# Digital__IO.net
KiCad netlist of a schematic drawn in Altium Designer
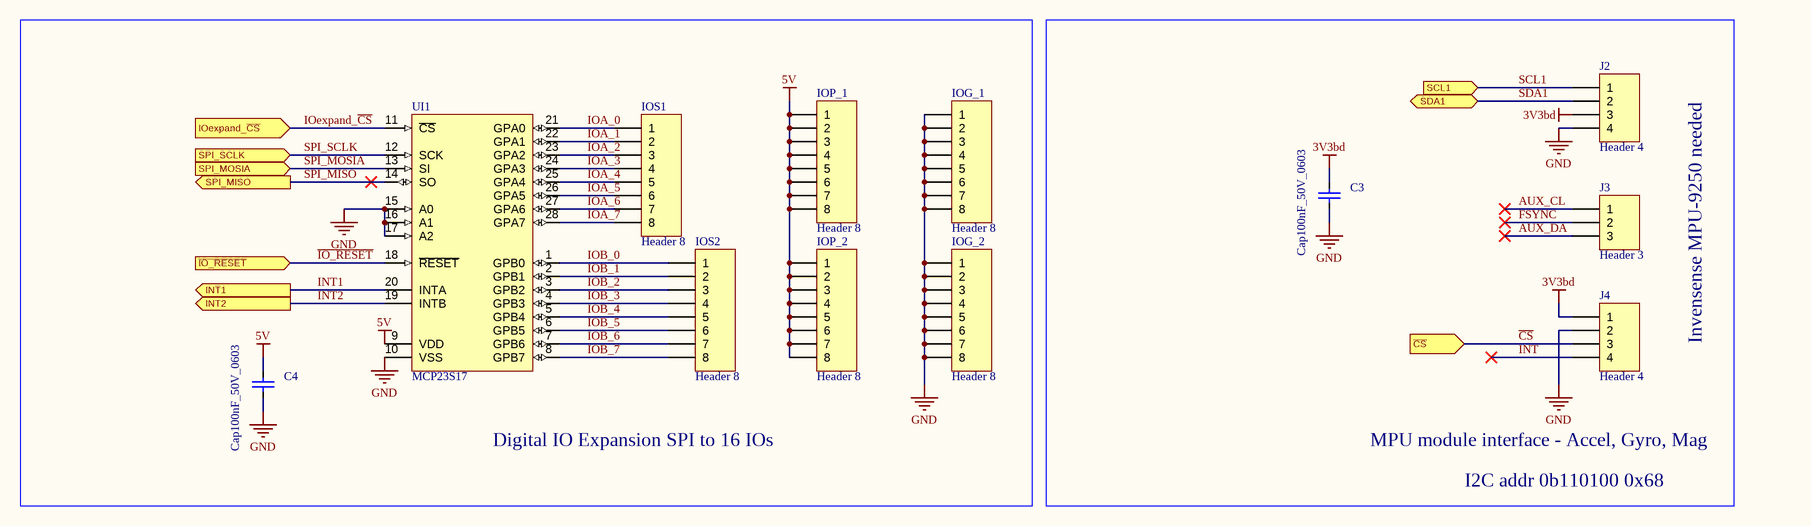
[diagram p0: Digital_ IO.SchDoc]

(export (version "E")
  (design (tool "Eeschema 10.0.6"))
  (components
    (comp (ref "C3")
      (value "Cap100nF_50V_0603")
      (footprint "0603C_L")
      (libsource (lib " Advanced] Training Course - A365") (part "CAP General"))
    )
    (comp (ref "C4")
      (value "Cap100nF_50V_0603")
      (footprint "0603C_L")
      (libsource (lib " Advanced] Training Course - A365") (part "CAP General"))
    )
    (comp (ref "IOG_1")
      (value "Header 8")
      (footprint "HDR1X8")
      (description "Header, 8-Pin")
      (fields (field (name "PUBLISHER") "Altium Limited") (field (name "SOURCE") "WCT.SchLib"))
      (libsource (lib " Advanced] Training Course - A365") (part "Header 8"))
    )
    (comp (ref "IOG_2")
      (value "Header 8")
      (footprint "HDR1X8")
      (description "Header, 8-Pin")
      (fields (field (name "PUBLISHER") "Altium Limited") (field (name "SOURCE") "WCT.SchLib"))
      (libsource (lib " Advanced] Training Course - A365") (part "Header 8"))
    )
    (comp (ref "IOP_1")
      (value "Header 8")
      (footprint "HDR1X8")
      (description "Header, 8-Pin")
      (fields (field (name "PUBLISHER") "Altium Limited") (field (name "SOURCE") "WCT.SchLib"))
      (libsource (lib " Advanced] Training Course - A365") (part "Header 8"))
    )
    (comp (ref "IOP_2")
      (value "Header 8")
      (footprint "HDR1X8")
      (description "Header, 8-Pin")
      (fields (field (name "PUBLISHER") "Altium Limited") (field (name "SOURCE") "WCT.SchLib"))
      (libsource (lib " Advanced] Training Course - A365") (part "Header 8"))
    )
    (comp (ref "IOS1")
      (value "Header 8")
      (footprint "HDR1X8")
      (description "Header, 8-Pin")
      (fields (field (name "PUBLISHER") "Altium Limited") (field (name "SOURCE") "WCT.SchLib"))
      (libsource (lib " Advanced] Training Course - A365") (part "Header 8"))
    )
    (comp (ref "IOS2")
      (value "Header 8")
      (footprint "HDR1X8")
      (description "Header, 8-Pin")
      (fields (field (name "PUBLISHER") "Altium Limited") (field (name "SOURCE") "WCT.SchLib"))
      (libsource (lib " Advanced] Training Course - A365") (part "Header 8"))
    )
    (comp (ref "J2")
      (value "Header 4")
      (footprint "HDR1X4")
      (description "Header, 4-Pin")
      (fields (field (name "PUBLISHER") "Altium Limited") (field (name "SOURCE") "WCT.SchLib"))
      (libsource (lib " Advanced] Training Course - A365") (part "Header 4"))
    )
    (comp (ref "J3")
      (value "Header 3")
      (footprint "HDR1X3")
      (description "Header, 3-Pin")
      (fields (field (name "PUBLISHER") "Altium Limited") (field (name "SOURCE") "WCT.SchLib"))
      (libsource (lib " Advanced] Training Course - A365") (part "Header 3"))
    )
    (comp (ref "J4")
      (value "Header 4")
      (footprint "HDR1X4")
      (description "Header, 4-Pin")
      (fields (field (name "PUBLISHER") "Altium Limited") (field (name "SOURCE") "WCT.SchLib"))
      (libsource (lib " Advanced] Training Course - A365") (part "Header 4"))
    )
    (comp (ref "UI1")
      (value "MCP23S17")
      (footprint "SOIC-SO28_L")
      (description "16-Bit I/O Expander with Serial Interface, 28-Pin SOIC, Extended Temperature, Tape and Reel")
      (fields
        (field (name "MANUFACTURER") "Microchip")
        (field (name "MANUFACTURER PART NUMBER") "MCP23S17T-E/SO")
        (field (name "AVAILABLE PREVIEW IMAGES") "2D")
        (field (name "SOURCE") "WCT.SchLib")
      )
      (libsource (lib " Advanced] Training Course - A365") (part "MCP23S17"))
    )
  )
  (nets
    (net (code "1") (name "/AUX_CL") (class "Default")
      (node (ref "J3") (pin "1") (pinfunction "1_1") (pintype "passive+no_connect"))
    )
    (net (code "2") (name "/AUX_DA") (class "Default")
      (node (ref "J3") (pin "3") (pinfunction "3_3") (pintype "passive+no_connect"))
    )
    (net (code "3") (name "/FSYNC") (class "Default")
      (node (ref "J3") (pin "2") (pinfunction "2_2") (pintype "passive+no_connect"))
    )
    (net (code "4") (name "/INT") (class "Default")
      (node (ref "J4") (pin "4") (pinfunction "4_4") (pintype "passive+no_connect"))
    )
    (net (code "5") (name "/INT1") (class "Default")
      (node (ref "UI1") (pin "20") (pinfunction "INTA_20") (pintype "open_collector"))
    )
    (net (code "6") (name "/INT2") (class "Default")
      (node (ref "UI1") (pin "19") (pinfunction "INTB_19") (pintype "open_collector"))
    )
    (net (code "7") (name "/IOA_0") (class "Default")
      (node (ref "IOS1") (pin "1") (pinfunction "1_1") (pintype "passive"))
      (node (ref "UI1") (pin "21") (pinfunction "GPA0_21") (pintype "bidirectional"))
    )
    (net (code "8") (name "/IOA_1") (class "Default")
      (node (ref "IOS1") (pin "2") (pinfunction "2_2") (pintype "passive"))
      (node (ref "UI1") (pin "22") (pinfunction "GPA1_22") (pintype "bidirectional"))
    )
    (net (code "9") (name "/IOA_2") (class "Default")
      (node (ref "IOS1") (pin "3") (pinfunction "3_3") (pintype "passive"))
      (node (ref "UI1") (pin "23") (pinfunction "GPA2_23") (pintype "bidirectional"))
    )
    (net (code "10") (name "/IOA_3") (class "Default")
      (node (ref "IOS1") (pin "4") (pinfunction "4_4") (pintype "passive"))
      (node (ref "UI1") (pin "24") (pinfunction "GPA3_24") (pintype "bidirectional"))
    )
    (net (code "11") (name "/IOA_4") (class "Default")
      (node (ref "IOS1") (pin "5") (pinfunction "5_5") (pintype "passive"))
      (node (ref "UI1") (pin "25") (pinfunction "GPA4_25") (pintype "bidirectional"))
    )
    (net (code "12") (name "/IOA_5") (class "Default")
      (node (ref "IOS1") (pin "6") (pinfunction "6_6") (pintype "passive"))
      (node (ref "UI1") (pin "26") (pinfunction "GPA5_26") (pintype "bidirectional"))
    )
    (net (code "13") (name "/IOA_6") (class "Default")
      (node (ref "IOS1") (pin "7") (pinfunction "7_7") (pintype "passive"))
      (node (ref "UI1") (pin "27") (pinfunction "GPA6_27") (pintype "bidirectional"))
    )
    (net (code "14") (name "/IOA_7") (class "Default")
      (node (ref "IOS1") (pin "8") (pinfunction "8_8") (pintype "passive"))
      (node (ref "UI1") (pin "28") (pinfunction "GPA7_28") (pintype "bidirectional"))
    )
    (net (code "15") (name "/IOB_0") (class "Default")
      (node (ref "IOS2") (pin "1") (pinfunction "1_1") (pintype "passive"))
      (node (ref "UI1") (pin "1") (pinfunction "GPB0_1") (pintype "bidirectional"))
    )
    (net (code "16") (name "/IOB_1") (class "Default")
      (node (ref "IOS2") (pin "2") (pinfunction "2_2") (pintype "passive"))
      (node (ref "UI1") (pin "2") (pinfunction "GPB1_2") (pintype "bidirectional"))
    )
    (net (code "17") (name "/IOB_2") (class "Default")
      (node (ref "IOS2") (pin "3") (pinfunction "3_3") (pintype "passive"))
      (node (ref "UI1") (pin "3") (pinfunction "GPB2_3") (pintype "bidirectional"))
    )
    (net (code "18") (name "/IOB_3") (class "Default")
      (node (ref "IOS2") (pin "4") (pinfunction "4_4") (pintype "passive"))
      (node (ref "UI1") (pin "4") (pinfunction "GPB3_4") (pintype "bidirectional"))
    )
    (net (code "19") (name "/IOB_4") (class "Default")
      (node (ref "IOS2") (pin "5") (pinfunction "5_5") (pintype "passive"))
      (node (ref "UI1") (pin "5") (pinfunction "GPB4_5") (pintype "bidirectional"))
    )
    (net (code "20") (name "/IOB_5") (class "Default")
      (node (ref "IOS2") (pin "6") (pinfunction "6_6") (pintype "passive"))
      (node (ref "UI1") (pin "6") (pinfunction "GPB5_6") (pintype "bidirectional"))
    )
    (net (code "21") (name "/IOB_6") (class "Default")
      (node (ref "IOS2") (pin "7") (pinfunction "7_7") (pintype "passive"))
      (node (ref "UI1") (pin "7") (pinfunction "GPB6_7") (pintype "bidirectional"))
    )
    (net (code "22") (name "/IOB_7") (class "Default")
      (node (ref "IOS2") (pin "8") (pinfunction "8_8") (pintype "passive"))
      (node (ref "UI1") (pin "8") (pinfunction "GPB7_8") (pintype "bidirectional"))
    )
    (net (code "23") (name "/IO_RESET") (class "Default")
      (node (ref "UI1") (pin "18") (pinfunction "~{RESET}_18") (pintype "input"))
    )
    (net (code "24") (name "/IOexpand_~{CS}") (class "Default")
      (node (ref "UI1") (pin "11") (pinfunction "~{CS}_11") (pintype "input"))
    )
    (net (code "25") (name "/SCL1") (class "Default")
      (node (ref "J2") (pin "1") (pinfunction "1_1") (pintype "passive"))
    )
    (net (code "26") (name "/SDA1") (class "Default")
      (node (ref "J2") (pin "2") (pinfunction "2_2") (pintype "passive"))
    )
    (net (code "27") (name "/SPI_MISO") (class "Default")
      (node (ref "UI1") (pin "14") (pinfunction "SO_14") (pintype "bidirectional"))
    )
    (net (code "28") (name "/SPI_MOSIA") (class "Default")
      (node (ref "UI1") (pin "13") (pinfunction "SI_13") (pintype "input"))
    )
    (net (code "29") (name "/SPI_SCLK") (class "Default")
      (node (ref "UI1") (pin "12") (pinfunction "SCK_12") (pintype "input"))
    )
    (net (code "30") (name "/~{CS}") (class "Default")
      (node (ref "J4") (pin "3") (pinfunction "3_3") (pintype "passive"))
    )
    (net (code "31") (name "3V3bd") (class "Default")
      (node (ref "C3") (pin "2") (pinfunction "2_2") (pintype "passive"))
      (node (ref "J2") (pin "3") (pinfunction "3_3") (pintype "passive"))
      (node (ref "J4") (pin "1") (pinfunction "1_1") (pintype "passive"))
    )
    (net (code "32") (name "5V") (class "Default")
      (node (ref "C4") (pin "2") (pinfunction "2_2") (pintype "passive"))
      (node (ref "IOP_1") (pin "1") (pinfunction "1_1") (pintype "passive"))
      (node (ref "IOP_1") (pin "2") (pinfunction "2_2") (pintype "passive"))
      (node (ref "IOP_1") (pin "3") (pinfunction "3_3") (pintype "passive"))
      (node (ref "IOP_1") (pin "4") (pinfunction "4_4") (pintype "passive"))
      (node (ref "IOP_1") (pin "5") (pinfunction "5_5") (pintype "passive"))
      (node (ref "IOP_1") (pin "6") (pinfunction "6_6") (pintype "passive"))
      (node (ref "IOP_1") (pin "7") (pinfunction "7_7") (pintype "passive"))
      (node (ref "IOP_1") (pin "8") (pinfunction "8_8") (pintype "passive"))
      (node (ref "IOP_2") (pin "1") (pinfunction "1_1") (pintype "passive"))
      (node (ref "IOP_2") (pin "2") (pinfunction "2_2") (pintype "passive"))
      (node (ref "IOP_2") (pin "3") (pinfunction "3_3") (pintype "passive"))
      (node (ref "IOP_2") (pin "4") (pinfunction "4_4") (pintype "passive"))
      (node (ref "IOP_2") (pin "5") (pinfunction "5_5") (pintype "passive"))
      (node (ref "IOP_2") (pin "6") (pinfunction "6_6") (pintype "passive"))
      (node (ref "IOP_2") (pin "7") (pinfunction "7_7") (pintype "passive"))
      (node (ref "IOP_2") (pin "8") (pinfunction "8_8") (pintype "passive"))
      (node (ref "UI1") (pin "9") (pinfunction "VDD_9") (pintype "power_in"))
    )
    (net (code "33") (name "GND") (class "Default")
      (node (ref "C3") (pin "1") (pinfunction "1_1") (pintype "passive"))
      (node (ref "C4") (pin "1") (pinfunction "1_1") (pintype "passive"))
      (node (ref "IOG_1") (pin "1") (pinfunction "1_1") (pintype "passive"))
      (node (ref "IOG_1") (pin "2") (pinfunction "2_2") (pintype "passive"))
      (node (ref "IOG_1") (pin "3") (pinfunction "3_3") (pintype "passive"))
      (node (ref "IOG_1") (pin "4") (pinfunction "4_4") (pintype "passive"))
      (node (ref "IOG_1") (pin "5") (pinfunction "5_5") (pintype "passive"))
      (node (ref "IOG_1") (pin "6") (pinfunction "6_6") (pintype "passive"))
      (node (ref "IOG_1") (pin "7") (pinfunction "7_7") (pintype "passive"))
      (node (ref "IOG_1") (pin "8") (pinfunction "8_8") (pintype "passive"))
      (node (ref "IOG_2") (pin "1") (pinfunction "1_1") (pintype "passive"))
      (node (ref "IOG_2") (pin "2") (pinfunction "2_2") (pintype "passive"))
      (node (ref "IOG_2") (pin "3") (pinfunction "3_3") (pintype "passive"))
      (node (ref "IOG_2") (pin "4") (pinfunction "4_4") (pintype "passive"))
      (node (ref "IOG_2") (pin "5") (pinfunction "5_5") (pintype "passive"))
      (node (ref "IOG_2") (pin "6") (pinfunction "6_6") (pintype "passive"))
      (node (ref "IOG_2") (pin "7") (pinfunction "7_7") (pintype "passive"))
      (node (ref "IOG_2") (pin "8") (pinfunction "8_8") (pintype "passive"))
      (node (ref "J2") (pin "4") (pinfunction "4_4") (pintype "passive"))
      (node (ref "J4") (pin "2") (pinfunction "2_2") (pintype "passive"))
      (node (ref "UI1") (pin "10") (pinfunction "VSS_10") (pintype "power_in"))
      (node (ref "UI1") (pin "15") (pinfunction "A0_15") (pintype "input"))
      (node (ref "UI1") (pin "16") (pinfunction "A1_16") (pintype "input"))
      (node (ref "UI1") (pin "17") (pinfunction "A2_17") (pintype "input"))
    )
  )
)
